# 2021.net
KiCad netlist of a schematic drawn in Altium Designer
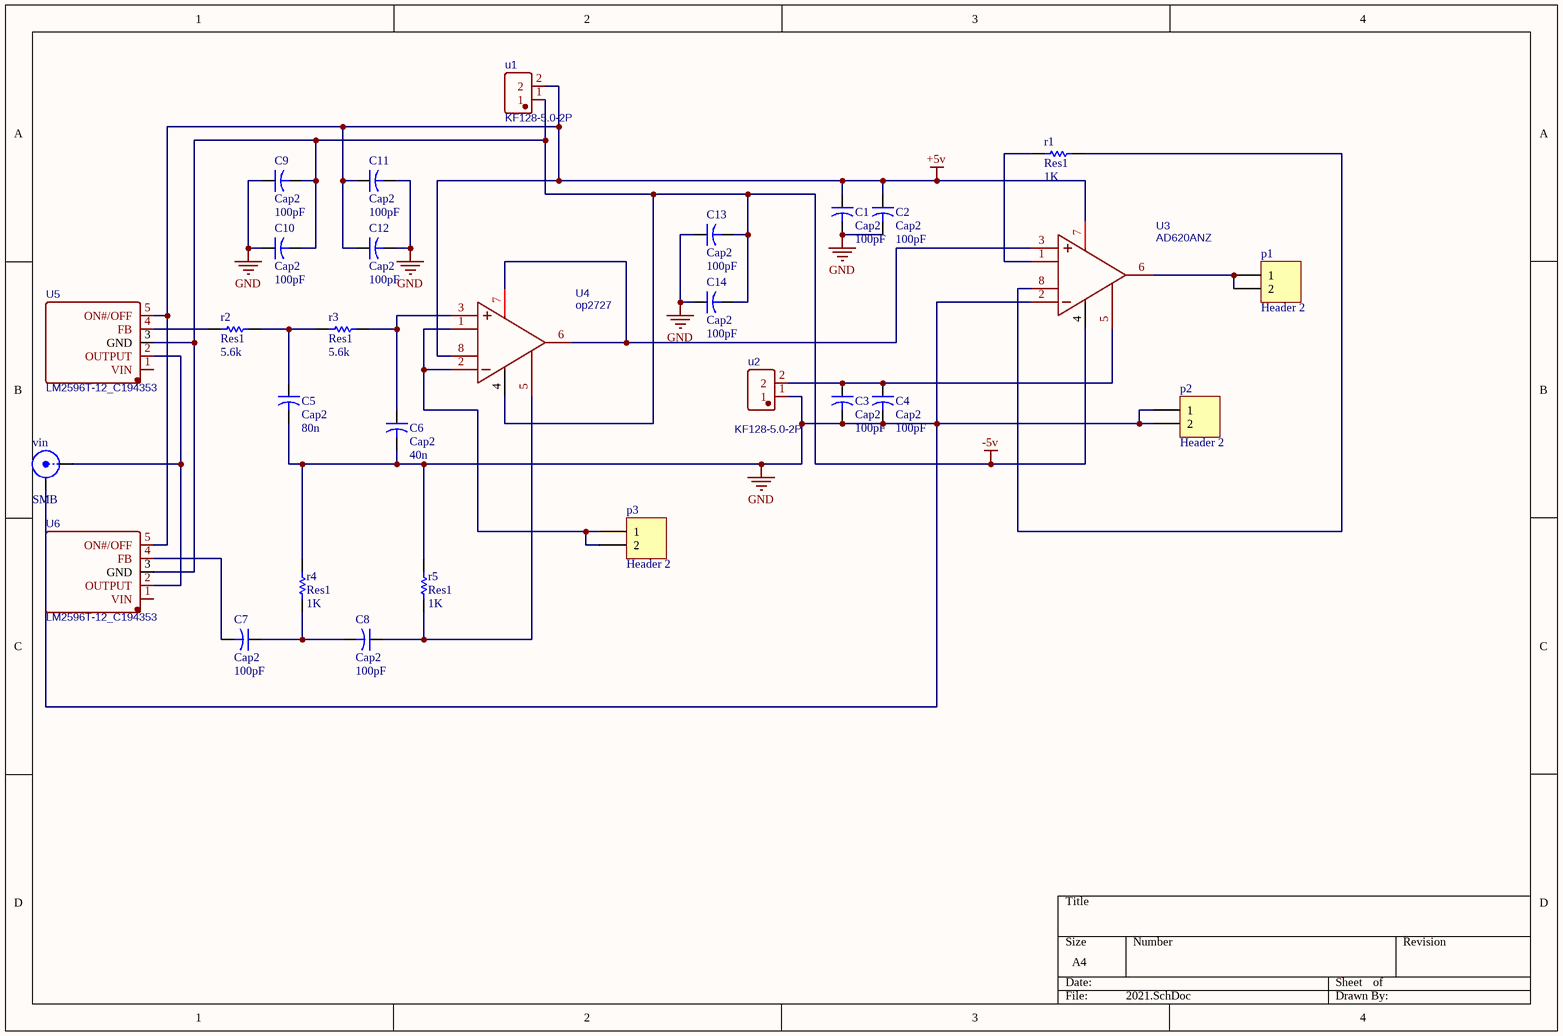
[diagram p0: 2021.SchDoc]

(export (version "E")
  (design (tool "Eeschema 10.0.6"))
  (components
    (comp (ref "C1")
      (value "Cap2")
      (footprint "CAPR5-4X5")
      (description "Capacitor")
      (fields (field (name "ALTIUM_VALUE") "100pF") (field (name "PUBLISHER") "Altium Limited"))
      (libsource (lib "Miscellaneous Devices") (part "Cap2"))
    )
    (comp (ref "C2")
      (value "Cap2")
      (footprint "CAPR5-4X5")
      (description "Capacitor")
      (fields (field (name "ALTIUM_VALUE") "100pF") (field (name "PUBLISHER") "Altium Limited"))
      (libsource (lib "Miscellaneous Devices") (part "Cap2"))
    )
    (comp (ref "C3")
      (value "Cap2")
      (footprint "CAPR5-4X5")
      (description "Capacitor")
      (fields (field (name "ALTIUM_VALUE") "100pF") (field (name "PUBLISHER") "Altium Limited"))
      (libsource (lib "Miscellaneous Devices") (part "Cap2"))
    )
    (comp (ref "C4")
      (value "Cap2")
      (footprint "CAPR5-4X5")
      (description "Capacitor")
      (fields (field (name "ALTIUM_VALUE") "100pF") (field (name "PUBLISHER") "Altium Limited"))
      (libsource (lib "Miscellaneous Devices") (part "Cap2"))
    )
    (comp (ref "C5")
      (value "Cap2")
      (footprint "CAPR5-4X5")
      (description "Capacitor")
      (fields (field (name "ALTIUM_VALUE") "80n") (field (name "PUBLISHER") "Altium Limited"))
      (libsource (lib "Miscellaneous Devices") (part "Cap2"))
    )
    (comp (ref "C6")
      (value "Cap2")
      (footprint "CAPR5-4X5")
      (description "Capacitor")
      (fields (field (name "ALTIUM_VALUE") "40n") (field (name "PUBLISHER") "Altium Limited"))
      (libsource (lib "Miscellaneous Devices") (part "Cap2"))
    )
    (comp (ref "C7")
      (value "Cap2")
      (footprint "CAPR5-4X5")
      (description "Capacitor")
      (fields (field (name "ALTIUM_VALUE") "100pF") (field (name "PUBLISHER") "Altium Limited"))
      (libsource (lib "Miscellaneous Devices") (part "Cap2"))
    )
    (comp (ref "C8")
      (value "Cap2")
      (footprint "CAPR5-4X5")
      (description "Capacitor")
      (fields (field (name "ALTIUM_VALUE") "100pF") (field (name "PUBLISHER") "Altium Limited"))
      (libsource (lib "Miscellaneous Devices") (part "Cap2"))
    )
    (comp (ref "C9")
      (value "Cap2")
      (footprint "CAPR5-4X5")
      (description "Capacitor")
      (fields (field (name "ALTIUM_VALUE") "100pF") (field (name "PUBLISHER") "Altium Limited"))
      (libsource (lib "Miscellaneous Devices") (part "Cap2"))
    )
    (comp (ref "C10")
      (value "Cap2")
      (footprint "CAPR5-4X5")
      (description "Capacitor")
      (fields (field (name "ALTIUM_VALUE") "100pF") (field (name "PUBLISHER") "Altium Limited"))
      (libsource (lib "Miscellaneous Devices") (part "Cap2"))
    )
    (comp (ref "C11")
      (value "Cap2")
      (footprint "CAPR5-4X5")
      (description "Capacitor")
      (fields (field (name "ALTIUM_VALUE") "100pF") (field (name "PUBLISHER") "Altium Limited"))
      (libsource (lib "Miscellaneous Devices") (part "Cap2"))
    )
    (comp (ref "C12")
      (value "Cap2")
      (footprint "CAPR5-4X5")
      (description "Capacitor")
      (fields (field (name "ALTIUM_VALUE") "100pF") (field (name "PUBLISHER") "Altium Limited"))
      (libsource (lib "Miscellaneous Devices") (part "Cap2"))
    )
    (comp (ref "C13")
      (value "Cap2")
      (footprint "CAPR5-4X5")
      (description "Capacitor")
      (fields (field (name "ALTIUM_VALUE") "100pF") (field (name "PUBLISHER") "Altium Limited"))
      (libsource (lib "Miscellaneous Devices") (part "Cap2"))
    )
    (comp (ref "C14")
      (value "Cap2")
      (footprint "CAPR5-4X5")
      (description "Capacitor")
      (fields (field (name "ALTIUM_VALUE") "100pF") (field (name "PUBLISHER") "Altium Limited"))
      (libsource (lib "Miscellaneous Devices") (part "Cap2"))
    )
    (comp (ref "p1")
      (value "Header 2")
      (footprint "HDR1X2")
      (description "Header, 2-Pin")
      (fields (field (name "PUBLISHER") "Altium Limited"))
      (libsource (lib "Miscellaneous Connectors") (part "Header 2"))
    )
    (comp (ref "p2")
      (value "Header 2")
      (footprint "HDR1X2")
      (description "Header, 2-Pin")
      (fields (field (name "PUBLISHER") "Altium Limited"))
      (libsource (lib "Miscellaneous Connectors") (part "Header 2"))
    )
    (comp (ref "p3")
      (value "Header 2")
      (footprint "HDR1X2")
      (description "Header, 2-Pin")
      (fields (field (name "PUBLISHER") "Altium Limited"))
      (libsource (lib "Miscellaneous Connectors") (part "Header 2"))
    )
    (comp (ref "r1")
      (value "Res1")
      (footprint "AXIAL-0.3")
      (description "Resistor")
      (fields (field (name "ALTIUM_VALUE") "1K") (field (name "PUBLISHER") "Altium Limited"))
      (libsource (lib "Miscellaneous Devices") (part "Res1"))
    )
    (comp (ref "r2")
      (value "Res1")
      (footprint "AXIAL-0.3")
      (description "Resistor")
      (fields (field (name "ALTIUM_VALUE") "5.6k") (field (name "PUBLISHER") "Altium Limited"))
      (libsource (lib "Miscellaneous Devices") (part "Res1"))
    )
    (comp (ref "r3")
      (value "Res1")
      (footprint "AXIAL-0.3")
      (description "Resistor")
      (fields (field (name "ALTIUM_VALUE") "5.6k") (field (name "PUBLISHER") "Altium Limited"))
      (libsource (lib "Miscellaneous Devices") (part "Res1"))
    )
    (comp (ref "r4")
      (value "Res1")
      (footprint "AXIAL-0.3")
      (description "Resistor")
      (fields (field (name "ALTIUM_VALUE") "1K") (field (name "PUBLISHER") "Altium Limited"))
      (libsource (lib "Miscellaneous Devices") (part "Res1"))
    )
    (comp (ref "r5")
      (value "Res1")
      (footprint "AXIAL-0.3")
      (description "Resistor")
      (fields (field (name "ALTIUM_VALUE") "1K") (field (name "PUBLISHER") "Altium Limited"))
      (libsource (lib "Miscellaneous Devices") (part "Res1"))
    )
    (comp (ref "u1")
      (value "KF128-5.0-2P")
      (footprint "CONN-TH_P5.00_KF128-5.0-2P")
      (fields (field (name "BOM_SUPPLIER PART") "C474950") (field (name "CONTRIBUTOR") "LCSC"))
      (libsource (lib "kf128") (part "KF128-5.0-2P"))
    )
    (comp (ref "u2")
      (value "KF128-5.0-2P")
      (footprint "CONN-TH_P5.00_KF128-5.0-2P")
      (fields (field (name "BOM_SUPPLIER PART") "C474950") (field (name "CONTRIBUTOR") "LCSC"))
      (libsource (lib "kf128") (part "KF128-5.0-2P"))
    )
    (comp (ref "U3")
      (value "AD620ANZ")
      (footprint "DIP-8_L9.3-W6.4-P2.54-LS7.6-BL")
      (fields (field (name "BOM_SUPPLIER PART") "C9680"))
      (libsource (lib "AD620ANZ") (part "AD620ANZ"))
    )
    (comp (ref "U4")
      (value "op2727")
      (footprint "DIP-8_L9.3-W6.4-P2.54-LS7.6-BL")
      (fields (field (name "BOM_MANUFACTURER PART") "AD620ANZ") (field (name "BOM_SUPPLIER PART") "C9680"))
      (libsource (lib "AD620ANZ") (part "AD620ANZ"))
    )
    (comp (ref "U5")
      (value "LM2596T-12_C194353")
      (footprint "TO-220-5L_L10.2-W4.5-P1.71-L")
      (fields
        (field (name "BOM_SUPPLIER PART") "C194353")
        (field (name "BOM_MANUFACTURER PART") "LM2596T-12")
        (field (name "CONTRIBUTOR") "LCSC")
      )
      (libsource (lib "to-220-5") (part "LM2596T-12_C194353"))
    )
    (comp (ref "U6")
      (value "LM2596T-12_C194353")
      (footprint "TO-220-5L_L10.2-W4.5-P1.71-L")
      (fields
        (field (name "BOM_SUPPLIER PART") "C194353")
        (field (name "BOM_MANUFACTURER PART") "LM2596T-12")
        (field (name "CONTRIBUTOR") "LCSC")
      )
      (libsource (lib "to-220-5") (part "LM2596T-12_C194353"))
    )
    (comp (ref "vin")
      (value "SMB")
      (footprint "SMB_V-RJ45")
      (description "SMB Straight Connector")
      (fields (field (name "PUBLISHER") "Altium Limited"))
      (libsource (lib "Miscellaneous Connectors") (part "SMB"))
    )
  )
  (nets
    (net (code "1") (name "+5v") (class "Default")
      (node (ref "C1") (pin "1") (pinfunction "1_1") (pintype "passive"))
      (node (ref "C11") (pin "1") (pinfunction "1_1") (pintype "passive"))
      (node (ref "C12") (pin "1") (pinfunction "1_1") (pintype "passive"))
      (node (ref "C2") (pin "1") (pinfunction "1_1") (pintype "passive"))
      (node (ref "U3") (pin "7") (pinfunction "+VS_7") (pintype "passive"))
      (node (ref "U4") (pin "8") (pinfunction "RG_8") (pintype "passive"))
      (node (ref "U5") (pin "5") (pinfunction "ON#/OFF_5") (pintype "passive"))
      (node (ref "U6") (pin "5") (pinfunction "ON#/OFF_5") (pintype "passive"))
      (node (ref "u1") (pin "2") (pinfunction "2_2") (pintype "passive"))
    )
    (net (code "2") (name "-5v") (class "Default")
      (node (ref "C10") (pin "2") (pinfunction "2_2") (pintype "passive"))
      (node (ref "C13") (pin "2") (pinfunction "2_2") (pintype "passive"))
      (node (ref "C14") (pin "2") (pinfunction "2_2") (pintype "passive"))
      (node (ref "C9") (pin "2") (pinfunction "2_2") (pintype "passive"))
      (node (ref "U3") (pin "4") (pinfunction "-VS_4") (pintype "passive"))
      (node (ref "U4") (pin "4") (pinfunction "-VS_4") (pintype "passive"))
      (node (ref "U5") (pin "3") (pinfunction "GND_3") (pintype "passive"))
      (node (ref "U6") (pin "3") (pinfunction "GND_3") (pintype "passive"))
      (node (ref "u1") (pin "1") (pinfunction "1_1") (pintype "passive"))
    )
    (net (code "3") (name "GND") (class "Default")
      (node (ref "C1") (pin "2") (pinfunction "2_2") (pintype "passive"))
      (node (ref "C10") (pin "1") (pinfunction "1_1") (pintype "passive"))
      (node (ref "C11") (pin "2") (pinfunction "2_2") (pintype "passive"))
      (node (ref "C12") (pin "2") (pinfunction "2_2") (pintype "passive"))
      (node (ref "C13") (pin "1") (pinfunction "1_1") (pintype "passive"))
      (node (ref "C14") (pin "1") (pinfunction "1_1") (pintype "passive"))
      (node (ref "C2") (pin "2") (pinfunction "2_2") (pintype "passive"))
      (node (ref "C3") (pin "2") (pinfunction "2_2") (pintype "passive"))
      (node (ref "C4") (pin "2") (pinfunction "2_2") (pintype "passive"))
      (node (ref "C5") (pin "2") (pinfunction "2_2") (pintype "passive"))
      (node (ref "C6") (pin "2") (pinfunction "2_2") (pintype "passive"))
      (node (ref "C9") (pin "1") (pinfunction "1_1") (pintype "passive"))
      (node (ref "U3") (pin "2") (pinfunction "-IN_2") (pintype "passive"))
      (node (ref "p2") (pin "1") (pinfunction "1_1") (pintype "passive"))
      (node (ref "p2") (pin "2") (pinfunction "2_2") (pintype "passive"))
      (node (ref "r4") (pin "2") (pinfunction "2_2") (pintype "passive"))
      (node (ref "r5") (pin "2") (pinfunction "2_2") (pintype "passive"))
      (node (ref "u2") (pin "1") (pinfunction "1_1") (pintype "passive"))
      (node (ref "vin") (pin "2") (pinfunction "Y_2") (pintype "passive"))
    )
    (net (code "4") (name "Net-(C5-Pad1)") (class "Default")
      (node (ref "C5") (pin "1") (pinfunction "1_1") (pintype "passive"))
      (node (ref "r2") (pin "2") (pinfunction "2_2") (pintype "passive"))
      (node (ref "r3") (pin "1") (pinfunction "1_1") (pintype "passive"))
    )
    (net (code "5") (name "Net-(C7-Pad1)") (class "Default")
      (node (ref "C7") (pin "1") (pinfunction "1_1") (pintype "passive"))
      (node (ref "C8") (pin "2") (pinfunction "2_2") (pintype "passive"))
      (node (ref "r4") (pin "1") (pinfunction "1_1") (pintype "passive"))
    )
    (net (code "6") (name "Net-(U3-+IN)") (class "Default")
      (node (ref "U3") (pin "3") (pinfunction "+IN_3") (pintype "passive"))
      (node (ref "U4") (pin "6") (pinfunction "OUTPUT_6") (pintype "passive"))
      (node (ref "U4") (pin "7") (pinfunction "+VS_7") (pintype "passive"))
    )
    (net (code "7") (name "Net-(U3-OUTPUT)") (class "Default")
      (node (ref "U3") (pin "6") (pinfunction "OUTPUT_6") (pintype "passive"))
      (node (ref "p1") (pin "1") (pinfunction "1_1") (pintype "passive"))
      (node (ref "p1") (pin "2") (pinfunction "2_2") (pintype "passive"))
    )
    (net (code "8") (name "Net-(U3-REF)") (class "Default")
      (node (ref "C3") (pin "1") (pinfunction "1_1") (pintype "passive"))
      (node (ref "C4") (pin "1") (pinfunction "1_1") (pintype "passive"))
      (node (ref "U3") (pin "5") (pinfunction "REF_5") (pintype "passive"))
      (node (ref "u2") (pin "2") (pinfunction "2_2") (pintype "passive"))
    )
    (net (code "9") (name "Net-(U3-RG-Pad1)") (class "Default")
      (node (ref "U3") (pin "1") (pinfunction "RG_1") (pintype "passive"))
      (node (ref "r1") (pin "1") (pinfunction "1_1") (pintype "passive"))
    )
    (net (code "10") (name "Net-(U3-RG-Pad8)") (class "Default")
      (node (ref "U3") (pin "8") (pinfunction "RG_8") (pintype "passive"))
      (node (ref "r1") (pin "2") (pinfunction "2_2") (pintype "passive"))
    )
    (net (code "11") (name "Net-(U4-+IN)") (class "Default")
      (node (ref "C6") (pin "1") (pinfunction "1_1") (pintype "passive"))
      (node (ref "U4") (pin "3") (pinfunction "+IN_3") (pintype "passive"))
      (node (ref "r3") (pin "2") (pinfunction "2_2") (pintype "passive"))
    )
    (net (code "12") (name "Net-(U4--IN)") (class "Default")
      (node (ref "U4") (pin "1") (pinfunction "RG_1") (pintype "passive"))
      (node (ref "U4") (pin "2") (pinfunction "-IN_2") (pintype "passive"))
      (node (ref "p3") (pin "1") (pinfunction "1_1") (pintype "passive"))
      (node (ref "p3") (pin "2") (pinfunction "2_2") (pintype "passive"))
    )
    (net (code "13") (name "Net-(U4-REF)") (class "Default")
      (node (ref "C8") (pin "1") (pinfunction "1_1") (pintype "passive"))
      (node (ref "U4") (pin "5") (pinfunction "REF_5") (pintype "passive"))
      (node (ref "r5") (pin "1") (pinfunction "1_1") (pintype "passive"))
    )
    (net (code "14") (name "Net-(U5-FB)") (class "Default")
      (node (ref "U5") (pin "4") (pinfunction "FB_4") (pintype "passive"))
      (node (ref "r2") (pin "1") (pinfunction "1_1") (pintype "passive"))
    )
    (net (code "15") (name "Net-(U5-OUTPUT)") (class "Default")
      (node (ref "U5") (pin "2") (pinfunction "OUTPUT_2") (pintype "passive"))
      (node (ref "U6") (pin "2") (pinfunction "OUTPUT_2") (pintype "passive"))
      (node (ref "vin") (pin "1") (pinfunction "X_1") (pintype "passive"))
    )
    (net (code "16") (name "Net-(U6-FB)") (class "Default")
      (node (ref "C7") (pin "2") (pinfunction "2_2") (pintype "passive"))
      (node (ref "U6") (pin "4") (pinfunction "FB_4") (pintype "passive"))
    )
    (net (code "17") (name "unconnected-(U5-VIN-Pad1)") (class "Default")
      (node (ref "U5") (pin "1") (pinfunction "VIN_1") (pintype "passive"))
    )
    (net (code "18") (name "unconnected-(U6-VIN-Pad1)") (class "Default")
      (node (ref "U6") (pin "1") (pinfunction "VIN_1") (pintype "passive"))
    )
  )
)
